# Arduino-Fio_v31.net
KiCad netlist of a schematic drawn in EAGLE
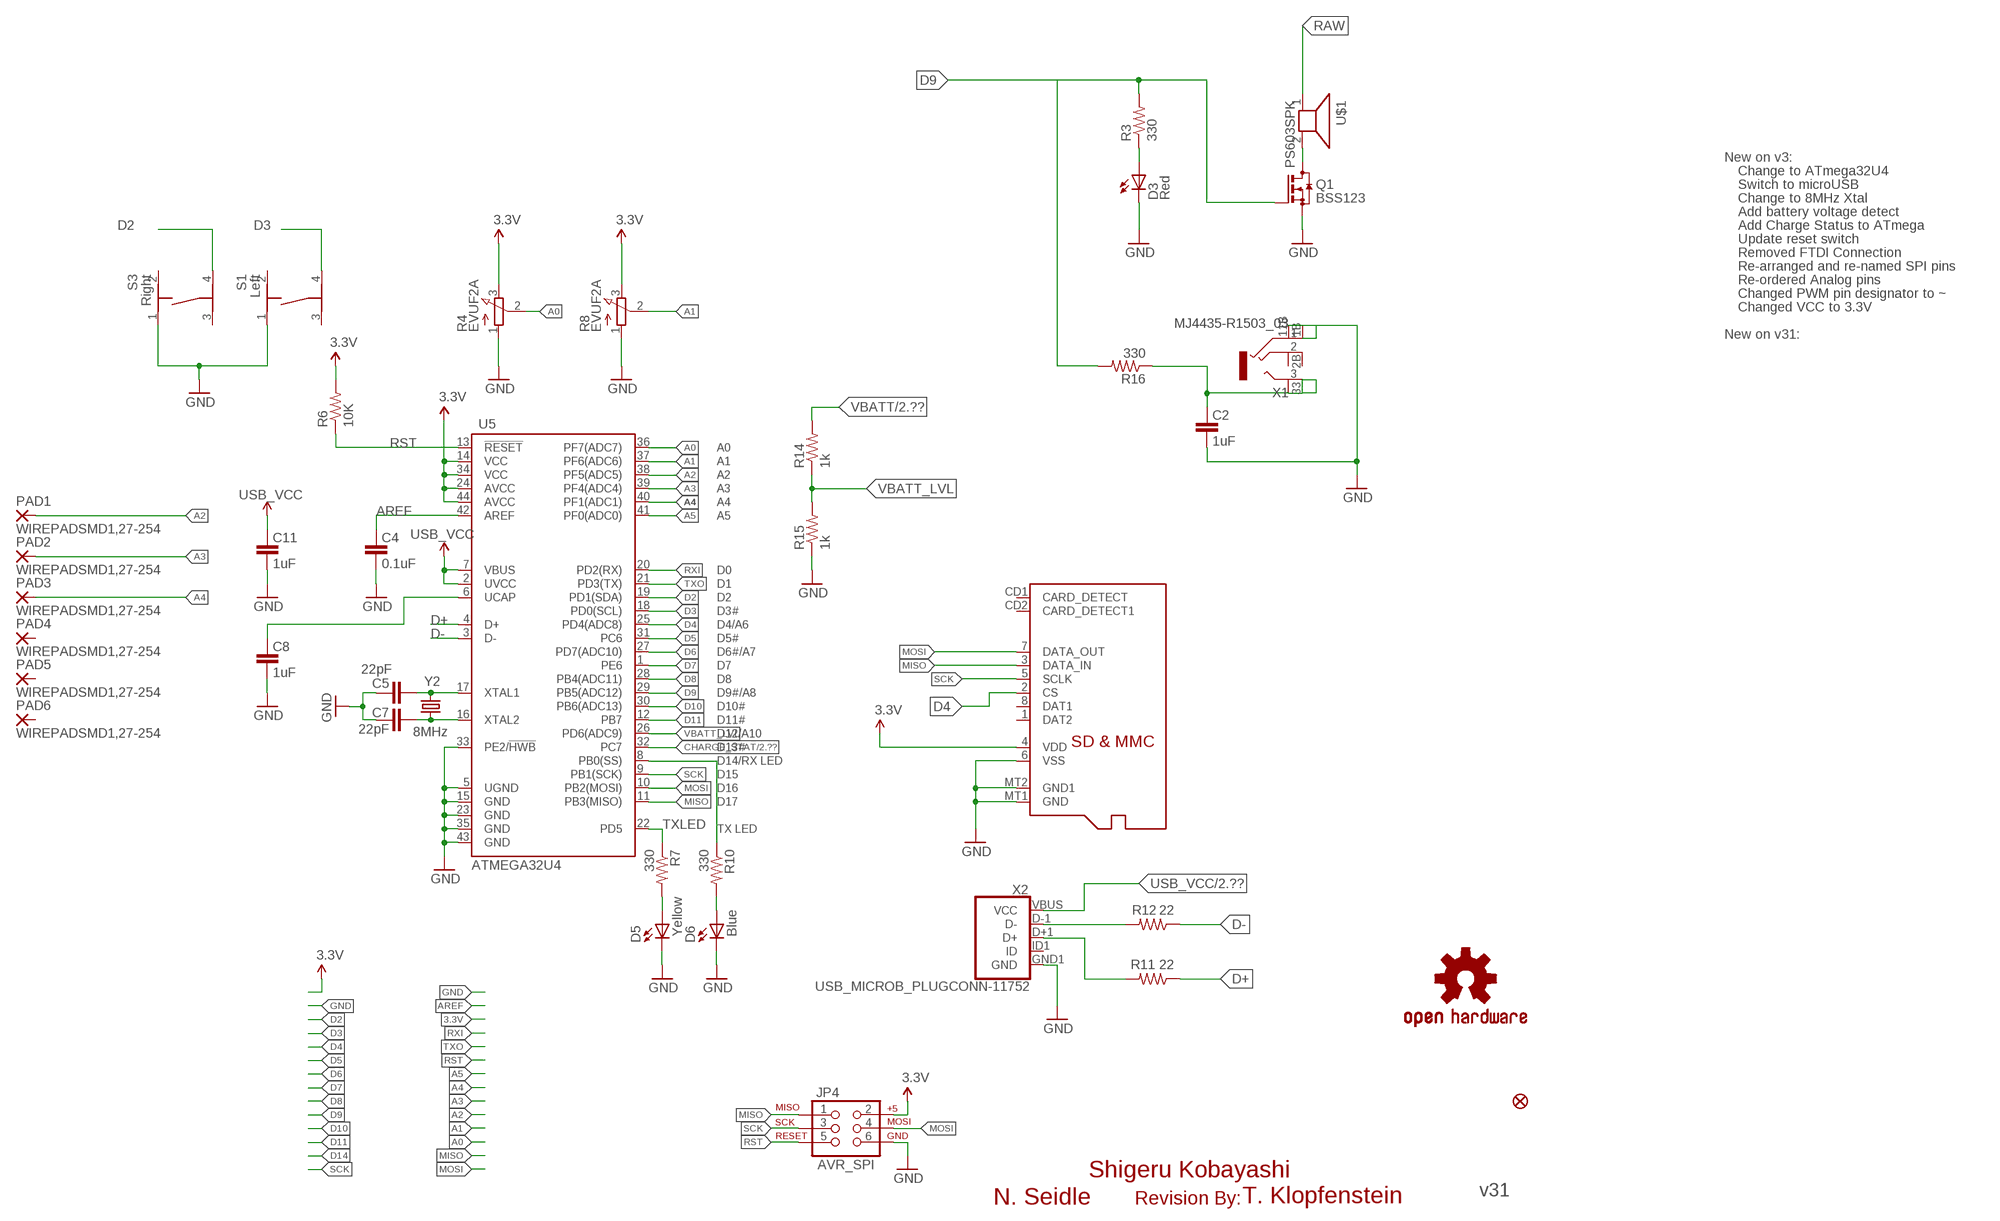
[diagram p0: schematic, sheet 1]
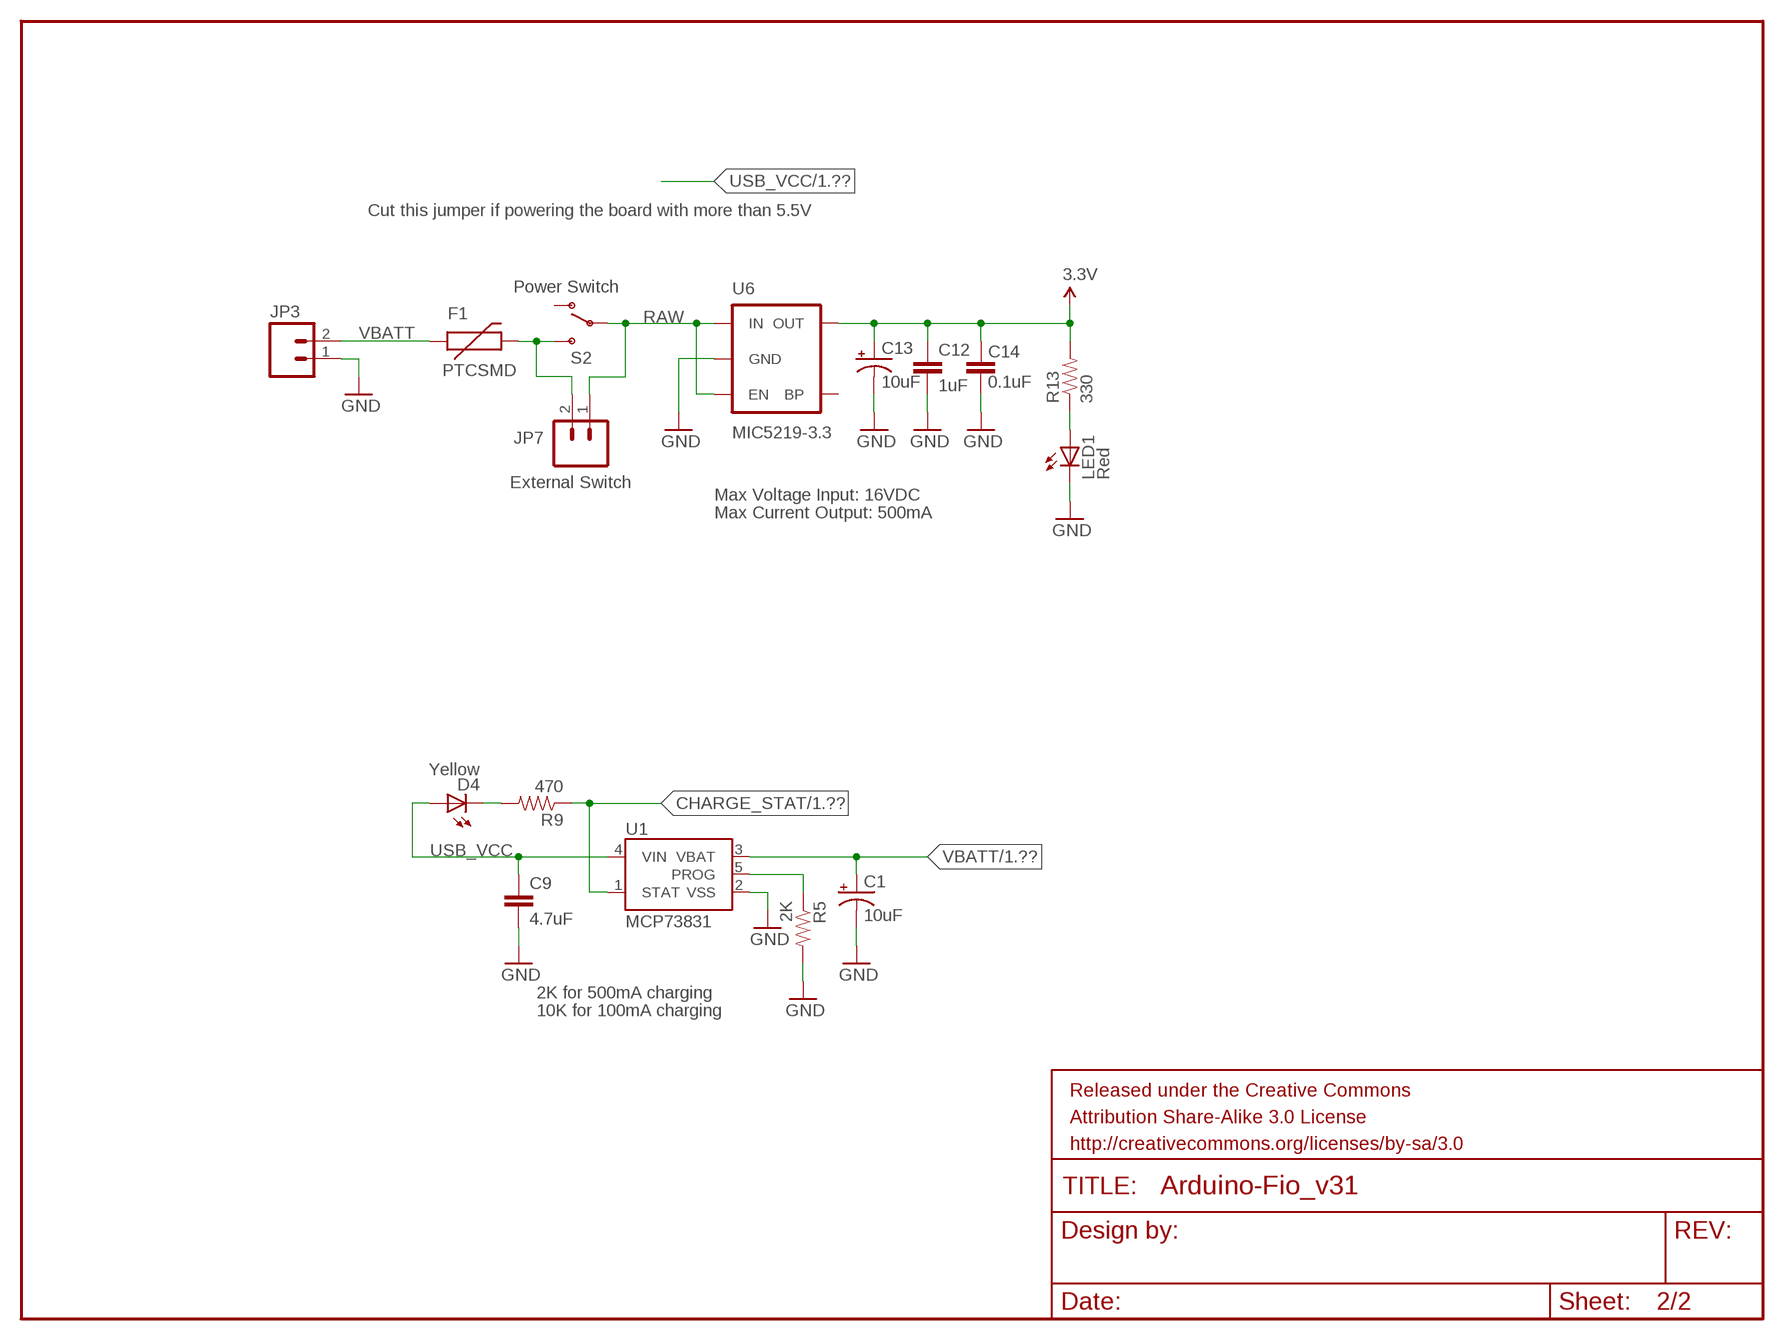
[diagram p1: schematic, sheet 2]

(export (version "E")
  (design (tool "Eeschema 10.0.6"))
  (components
    (comp (ref "C2")
      (value "1uF")
      (footprint "eagle-import:0603-CAP")
      (libsource (lib "eagle-import") (part "CAP0603-CAP"))
    )
    (comp (ref "C4")
      (value "0.1uF")
      (footprint "eagle-import:0603-CAP")
      (libsource (lib "eagle-import") (part "CAP0603-CAP"))
    )
    (comp (ref "C5")
      (value "22pF")
      (footprint "eagle-import:0603-CAP")
      (libsource (lib "eagle-import") (part "CAP0603-CAP"))
    )
    (comp (ref "C7")
      (value "22pF")
      (footprint "eagle-import:0603-CAP")
      (libsource (lib "eagle-import") (part "CAP0603-CAP"))
    )
    (comp (ref "C8")
      (value "1uF")
      (footprint "eagle-import:0603-CAP")
      (libsource (lib "eagle-import") (part "CAP0603-CAP"))
    )
    (comp (ref "C11")
      (value "1uF")
      (footprint "eagle-import:0603-CAP")
      (libsource (lib "eagle-import") (part "CAP0603-CAP"))
    )
    (comp (ref "D3")
      (value "Red")
      (footprint "eagle-import:LED-0603")
      (libsource (lib "eagle-import") (part "LED0603"))
    )
    (comp (ref "D5")
      (value "Yellow")
      (footprint "eagle-import:LED-0603")
      (libsource (lib "eagle-import") (part "LED0603"))
    )
    (comp (ref "D6")
      (value "Blue")
      (footprint "eagle-import:LED-0603")
      (libsource (lib "eagle-import") (part "LED0603"))
    )
    (comp (ref "JP4")
      (value "AVR_SPI")
      (footprint "eagle-import:2X3")
      (libsource (lib "eagle-import") (part "AVR_SPI_PRG_6PTH"))
    )
    (comp (ref "JP10")
      (value "FIDUCIALUFIDUCIAL")
      (footprint "eagle-import:FIDUCIAL-1X2")
      (libsource (lib "eagle-import") (part "FIDUCIAL1X2"))
    )
    (comp (ref "LOGO1")
      (value "OSHW-LOGOL")
      (footprint "eagle-import:OSHW-LOGO-L")
      (libsource (lib "eagle-import") (part "OSHW-LOGOL"))
    )
    (comp (ref "PAD1")
      (value "WIREPADSMD1,27-254")
      (footprint "eagle-import:SMD1,27-2,54")
      (libsource (lib "eagle-import") (part "WIREPADSMD1,27-254"))
    )
    (comp (ref "PAD2")
      (value "WIREPADSMD1,27-254")
      (footprint "eagle-import:SMD1,27-2,54")
      (libsource (lib "eagle-import") (part "WIREPADSMD1,27-254"))
    )
    (comp (ref "PAD3")
      (value "WIREPADSMD1,27-254")
      (footprint "eagle-import:SMD1,27-2,54")
      (libsource (lib "eagle-import") (part "WIREPADSMD1,27-254"))
    )
    (comp (ref "PAD4")
      (value "WIREPADSMD1,27-254")
      (footprint "eagle-import:SMD1,27-2,54")
      (libsource (lib "eagle-import") (part "WIREPADSMD1,27-254"))
    )
    (comp (ref "PAD5")
      (value "WIREPADSMD1,27-254")
      (footprint "eagle-import:SMD1,27-2,54")
      (libsource (lib "eagle-import") (part "WIREPADSMD1,27-254"))
    )
    (comp (ref "PAD6")
      (value "WIREPADSMD1,27-254")
      (footprint "eagle-import:SMD1,27-2,54")
      (libsource (lib "eagle-import") (part "WIREPADSMD1,27-254"))
    )
    (comp (ref "Q1")
      (value "BSS123")
      (footprint "eagle-import:SOT23")
      (libsource (lib "eagle-import") (part "BSS123"))
    )
    (comp (ref "R3")
      (value "330")
      (footprint "eagle-import:0603-RES")
      (libsource (lib "eagle-import") (part "RESISTOR0603-RES"))
    )
    (comp (ref "R4")
      (value "EVUF2A")
      (footprint "eagle-import:EVUF")
      (libsource (lib "eagle-import") (part "EVUAF2"))
    )
    (comp (ref "R6")
      (value "10K")
      (footprint "eagle-import:0603-RES")
      (libsource (lib "eagle-import") (part "RESISTOR0603-RES"))
    )
    (comp (ref "R7")
      (value "330")
      (footprint "eagle-import:0603-RES")
      (libsource (lib "eagle-import") (part "RESISTOR0603-RES"))
    )
    (comp (ref "R8")
      (value "EVUF2A")
      (footprint "eagle-import:EVUF")
      (libsource (lib "eagle-import") (part "EVUAF2"))
    )
    (comp (ref "R10")
      (value "330")
      (footprint "eagle-import:0603-RES")
      (libsource (lib "eagle-import") (part "RESISTOR0603-RES"))
    )
    (comp (ref "R11")
      (value "22")
      (footprint "eagle-import:0603-RES")
      (libsource (lib "eagle-import") (part "RESISTOR0603-RES"))
    )
    (comp (ref "R12")
      (value "22")
      (footprint "eagle-import:0603-RES")
      (libsource (lib "eagle-import") (part "RESISTOR0603-RES"))
    )
    (comp (ref "R14")
      (value "1k")
      (footprint "eagle-import:0603-RES")
      (libsource (lib "eagle-import") (part "RESISTOR0603-RES"))
    )
    (comp (ref "R15")
      (value "1k")
      (footprint "eagle-import:0603-RES")
      (libsource (lib "eagle-import") (part "RESISTOR0603-RES"))
    )
    (comp (ref "R16")
      (value "330")
      (footprint "eagle-import:0603-RES")
      (libsource (lib "eagle-import") (part "RESISTOR0603-RES"))
    )
    (comp (ref "S1")
      (value "Left")
      (footprint "eagle-import:TASTER-9314_SMD")
      (libsource (lib "eagle-import") (part "TASTER-9314_SMD"))
    )
    (comp (ref "S3")
      (value "Right")
      (footprint "eagle-import:TASTER-9314_SMD")
      (libsource (lib "eagle-import") (part "TASTER-9314_SMD"))
    )
    (comp (ref "U$1")
      (value "PS603SPK")
      (footprint "eagle-import:PS603")
      (libsource (lib "eagle-import") (part "PS603SPK"))
    )
    (comp (ref "U$2")
      (value "REVISION")
      (footprint "eagle-import:REVISION")
      (libsource (lib "eagle-import") (part "REVISION"))
    )
    (comp (ref "U$3")
      (value "MICROSD")
      (footprint "eagle-import:MICROSD")
      (libsource (lib "eagle-import") (part "MICROSD"))
    )
    (comp (ref "U5")
      (value "ATMEGA32U4")
      (footprint "eagle-import:QFN-44-NOPAD_1_1")
      (libsource (lib "eagle-import") (part "ATMEGA32U41{colon}1"))
    )
    (comp (ref "X1")
      (value "MJ4435-R1503_03")
      (footprint "eagle-import:1503_02")
      (libsource (lib "eagle-import") (part "MJ4435-R1503_03"))
    )
    (comp (ref "X2")
      (value "USB_MICROB_PLUGCONN-11752")
      (footprint "eagle-import:USB-B-MICRO-SMD_V03")
      (libsource (lib "eagle-import") (part "USB_MICROB_PLUGCONN-11752"))
    )
    (comp (ref "Y2")
      (value "8MHz")
      (footprint "eagle-import:CRYSTAL-SMD-5X3")
      (libsource (lib "eagle-import") (part "CRYSTAL5X3"))
    )
    (comp (ref "C1")
      (value "10uF")
      (footprint "eagle-import:EIA3216")
      (libsource (lib "eagle-import") (part "CAP_POL1206"))
    )
    (comp (ref "C9")
      (value "4.7uF")
      (footprint "eagle-import:0603-CAP")
      (libsource (lib "eagle-import") (part "CAP0603-CAP"))
    )
    (comp (ref "C12")
      (value "1uF")
      (footprint "eagle-import:0603-CAP")
      (libsource (lib "eagle-import") (part "CAP0603-CAP"))
    )
    (comp (ref "C13")
      (value "10uF")
      (footprint "eagle-import:EIA3216")
      (libsource (lib "eagle-import") (part "CAP_POL1206"))
    )
    (comp (ref "C14")
      (value "0.1uF")
      (footprint "eagle-import:0603-CAP")
      (libsource (lib "eagle-import") (part "CAP0603-CAP"))
    )
    (comp (ref "D4")
      (value "Yellow")
      (footprint "eagle-import:LED-0603")
      (libsource (lib "eagle-import") (part "LED0603"))
    )
    (comp (ref "F1")
      (value "PTCSMD")
      (footprint "eagle-import:PTC-1206")
      (libsource (lib "eagle-import") (part "PTCSMD"))
    )
    (comp (ref "FRAME2")
      (value "FRAME-LETTER")
      (footprint "eagle-import:CREATIVE_COMMONS")
      (libsource (lib "eagle-import") (part "FRAME-LETTER"))
    )
    (comp (ref "JP3")
      (value "M02-JST-2MM-SMT")
      (footprint "eagle-import:JST-2-SMD")
      (libsource (lib "eagle-import") (part "M02-JST-2MM-SMT"))
    )
    (comp (ref "JP7")
      (value "External Switch")
      (footprint "eagle-import:1X02")
      (libsource (lib "eagle-import") (part "M02PTH"))
    )
    (comp (ref "LED1")
      (value "Red")
      (footprint "eagle-import:LED-0603")
      (libsource (lib "eagle-import") (part "LED0603"))
    )
    (comp (ref "R5")
      (value "2K")
      (footprint "eagle-import:0603-RES")
      (libsource (lib "eagle-import") (part "RESISTOR0603-RES"))
    )
    (comp (ref "R9")
      (value "470")
      (footprint "eagle-import:0603-RES")
      (libsource (lib "eagle-import") (part "RESISTOR0603-RES"))
    )
    (comp (ref "R13")
      (value "330")
      (footprint "eagle-import:0603-RES")
      (libsource (lib "eagle-import") (part "RESISTOR0603-RES"))
    )
    (comp (ref "S2")
      (value "Power Switch")
      (footprint "eagle-import:AYZ0202")
      (libsource (lib "eagle-import") (part "SWITCH-SPSTSMD"))
    )
    (comp (ref "U1")
      (value "MCP73831")
      (footprint "eagle-import:SOT23-5")
      (libsource (lib "eagle-import") (part "MCP73831"))
    )
    (comp (ref "U6")
      (value "MIC5219-3.3")
      (footprint "eagle-import:SOT23-5")
      (libsource (lib "eagle-import") (part "V_REG_LDOSMD"))
    )
  )
  (nets
    (net (code "1") (name "3.3V") (class "Default")
      (node (ref "C12") (pin "1") (pinfunction "1_1") (pintype "passive"))
      (node (ref "C13") (pin "A") (pinfunction "+_A") (pintype "passive"))
      (node (ref "C14") (pin "2") (pinfunction "2_2") (pintype "passive"))
      (node (ref "JP4") (pin "2") (pinfunction "2_2") (pintype "passive"))
      (node (ref "R13") (pin "2") (pinfunction "2_2") (pintype "passive"))
      (node (ref "R4") (pin "3") (pinfunction "E_3") (pintype "passive"))
      (node (ref "R6") (pin "2") (pinfunction "2_2") (pintype "passive"))
      (node (ref "R8") (pin "3") (pinfunction "E_3") (pintype "passive"))
      (node (ref "U$3") (pin "4") (pinfunction "VDD_4") (pintype "power_in"))
      (node (ref "U5") (pin "14") (pinfunction "VCC_14") (pintype "bidirectional"))
      (node (ref "U5") (pin "24") (pinfunction "AVCC_24") (pintype "bidirectional"))
      (node (ref "U5") (pin "34") (pinfunction "VCC_34") (pintype "bidirectional"))
      (node (ref "U5") (pin "44") (pinfunction "AVCC_44") (pintype "bidirectional"))
      (node (ref "U6") (pin "5") (pinfunction "OUT_5") (pintype "passive"))
    )
    (net (code "2") (name "A0") (class "Default")
      (node (ref "R4") (pin "2") (pinfunction "S_2") (pintype "passive"))
      (node (ref "U5") (pin "36") (pinfunction "PF7(ADC7)_36") (pintype "bidirectional"))
    )
    (net (code "3") (name "A1") (class "Default")
      (node (ref "R8") (pin "2") (pinfunction "S_2") (pintype "passive"))
      (node (ref "U5") (pin "37") (pinfunction "PF6(ADC6)_37") (pintype "bidirectional"))
    )
    (net (code "4") (name "A2") (class "Default")
      (node (ref "PAD1") (pin "1") (pinfunction "P_1") (pintype "passive"))
      (node (ref "U5") (pin "38") (pinfunction "PF5(ADC5)_38") (pintype "bidirectional"))
    )
    (net (code "5") (name "A3") (class "Default")
      (node (ref "PAD2") (pin "1") (pinfunction "P_1") (pintype "passive"))
      (node (ref "U5") (pin "39") (pinfunction "PF4(ADC4)_39") (pintype "bidirectional"))
    )
    (net (code "6") (name "A4") (class "Default")
      (node (ref "PAD3") (pin "1") (pinfunction "P_1") (pintype "passive"))
      (node (ref "U5") (pin "40") (pinfunction "PF1(ADC1)_40") (pintype "bidirectional"))
    )
    (net (code "7") (name "A5") (class "Default")
      (node (ref "U5") (pin "41") (pinfunction "PF0(ADC0)_41") (pintype "bidirectional"))
    )
    (net (code "8") (name "AREF") (class "Default")
      (node (ref "C4") (pin "2") (pinfunction "2_2") (pintype "passive"))
      (node (ref "U5") (pin "42") (pinfunction "AREF_42") (pintype "bidirectional"))
    )
    (net (code "9") (name "CHARGE_STAT") (class "Default")
      (node (ref "R9") (pin "1") (pinfunction "1_1") (pintype "passive"))
      (node (ref "U1") (pin "1") (pinfunction "STAT_1") (pintype "output"))
      (node (ref "U5") (pin "32") (pinfunction "PC7_32") (pintype "bidirectional"))
    )
    (net (code "10") (name "D+") (class "Default")
      (node (ref "R11") (pin "1") (pinfunction "1_1") (pintype "passive"))
      (node (ref "U5") (pin "4") (pinfunction "D+_4") (pintype "bidirectional"))
    )
    (net (code "11") (name "D-") (class "Default")
      (node (ref "R12") (pin "1") (pinfunction "1_1") (pintype "passive"))
      (node (ref "U5") (pin "3") (pinfunction "D-_3") (pintype "bidirectional"))
    )
    (net (code "12") (name "D2") (class "Default")
      (node (ref "S3") (pin "4") (pinfunction "4_4") (pintype "passive"))
      (node (ref "U5") (pin "19") (pinfunction "PD1(SDA)_19") (pintype "bidirectional"))
    )
    (net (code "13") (name "D3") (class "Default")
      (node (ref "S1") (pin "4") (pinfunction "4_4") (pintype "passive"))
      (node (ref "U5") (pin "18") (pinfunction "PD0(SCL)_18") (pintype "bidirectional"))
    )
    (net (code "14") (name "D4") (class "Default")
      (node (ref "U$3") (pin "2") (pinfunction "CS_2") (pintype "input"))
      (node (ref "U5") (pin "25") (pinfunction "PD4(ADC8)_25") (pintype "bidirectional"))
    )
    (net (code "15") (name "D5") (class "Default")
      (node (ref "U5") (pin "31") (pinfunction "PC6_31") (pintype "bidirectional"))
    )
    (net (code "16") (name "D6") (class "Default")
      (node (ref "U5") (pin "27") (pinfunction "PD7(ADC10)_27") (pintype "bidirectional"))
    )
    (net (code "17") (name "D7") (class "Default")
      (node (ref "U5") (pin "1") (pinfunction "PE6_1") (pintype "bidirectional"))
    )
    (net (code "18") (name "D8") (class "Default")
      (node (ref "U5") (pin "28") (pinfunction "PB4(ADC11)_28") (pintype "bidirectional"))
    )
    (net (code "19") (name "D9") (class "Default")
      (node (ref "Q1") (pin "1") (pinfunction "G_1") (pintype "passive"))
      (node (ref "R16") (pin "2") (pinfunction "2_2") (pintype "passive"))
      (node (ref "R3") (pin "2") (pinfunction "2_2") (pintype "passive"))
      (node (ref "U5") (pin "29") (pinfunction "PB5(ADC12)_29") (pintype "bidirectional"))
    )
    (net (code "20") (name "D10") (class "Default")
      (node (ref "U5") (pin "30") (pinfunction "PB6(ADC13)_30") (pintype "bidirectional"))
    )
    (net (code "21") (name "D11") (class "Default")
      (node (ref "U5") (pin "12") (pinfunction "PB7_12") (pintype "bidirectional"))
    )
    (net (code "22") (name "D14") (class "Default")
      (node (ref "R10") (pin "1") (pinfunction "1_1") (pintype "passive"))
      (node (ref "U5") (pin "8") (pinfunction "PB0(SS)_8") (pintype "bidirectional"))
    )
    (net (code "23") (name "GND") (class "Default")
      (node (ref "C1") (pin "C") (pinfunction "-_C") (pintype "passive"))
      (node (ref "C11") (pin "1") (pinfunction "1_1") (pintype "passive"))
      (node (ref "C12") (pin "2") (pinfunction "2_2") (pintype "passive"))
      (node (ref "C13") (pin "C") (pinfunction "-_C") (pintype "passive"))
      (node (ref "C14") (pin "1") (pinfunction "1_1") (pintype "passive"))
      (node (ref "C2") (pin "1") (pinfunction "1_1") (pintype "passive"))
      (node (ref "C4") (pin "1") (pinfunction "1_1") (pintype "passive"))
      (node (ref "C5") (pin "2") (pinfunction "2_2") (pintype "passive"))
      (node (ref "C7") (pin "2") (pinfunction "2_2") (pintype "passive"))
      (node (ref "C8") (pin "1") (pinfunction "1_1") (pintype "passive"))
      (node (ref "C9") (pin "2") (pinfunction "2_2") (pintype "passive"))
      (node (ref "D3") (pin "C") (pinfunction "C_C") (pintype "passive"))
      (node (ref "D5") (pin "C") (pinfunction "C_C") (pintype "passive"))
      (node (ref "D6") (pin "C") (pinfunction "C_C") (pintype "passive"))
      (node (ref "JP3") (pin "1") (pinfunction "1_1") (pintype "passive"))
      (node (ref "JP4") (pin "6") (pinfunction "6_6") (pintype "passive"))
      (node (ref "LED1") (pin "C") (pinfunction "C_C") (pintype "passive"))
      (node (ref "Q1") (pin "2") (pinfunction "S_2") (pintype "passive"))
      (node (ref "R15") (pin "1") (pinfunction "1_1") (pintype "passive"))
      (node (ref "R4") (pin "1") (pinfunction "A_1") (pintype "passive"))
      (node (ref "R5") (pin "2") (pinfunction "2_2") (pintype "passive"))
      (node (ref "R8") (pin "1") (pinfunction "A_1") (pintype "passive"))
      (node (ref "S1") (pin "1") (pinfunction "1_1") (pintype "passive"))
      (node (ref "S3") (pin "1") (pinfunction "1_1") (pintype "passive"))
      (node (ref "U$3") (pin "6") (pinfunction "VSS_6") (pintype "power_in"))
      (node (ref "U$3") (pin "MT1") (pinfunction "GND_MT1") (pintype "power_in"))
      (node (ref "U$3") (pin "MT2") (pinfunction "GND1_MT2") (pintype "power_in"))
      (node (ref "U1") (pin "2") (pinfunction "VSS_2") (pintype "power_in"))
      (node (ref "U5") (pin "15") (pinfunction "GND_15") (pintype "bidirectional"))
      (node (ref "U5") (pin "23") (pinfunction "GND_23") (pintype "bidirectional"))
      (node (ref "U5") (pin "33") (pinfunction "PE2/~{HWB}_33") (pintype "bidirectional"))
      (node (ref "U5") (pin "35") (pinfunction "GND_35") (pintype "bidirectional"))
      (node (ref "U5") (pin "43") (pinfunction "GND_43") (pintype "bidirectional"))
      (node (ref "U5") (pin "5") (pinfunction "UGND_5") (pintype "bidirectional"))
      (node (ref "U6") (pin "2") (pinfunction "GND_2") (pintype "input"))
      (node (ref "X1") (pin "1") (pinfunction "1_1_1") (pintype "passive"))
      (node (ref "X1") (pin "11B") (pinfunction "1_4_11B") (pintype "passive"))
      (node (ref "X1") (pin "1B") (pinfunction "1_3_1B") (pintype "passive"))
      (node (ref "X2") (pin "GND1") (pinfunction "GND_GND1") (pintype "bidirectional"))
    )
    (net (code "24") (name "MISO") (class "Default")
      (node (ref "JP4") (pin "1") (pinfunction "1_1") (pintype "passive"))
      (node (ref "U$3") (pin "3") (pinfunction "DATA_IN_3") (pintype "input"))
      (node (ref "U5") (pin "11") (pinfunction "PB3(MISO)_11") (pintype "bidirectional"))
    )
    (net (code "25") (name "MOSI") (class "Default")
      (node (ref "JP4") (pin "4") (pinfunction "4_4") (pintype "passive"))
      (node (ref "U$3") (pin "7") (pinfunction "DATA_OUT_7") (pintype "output"))
      (node (ref "U5") (pin "10") (pinfunction "PB2(MOSI)_10") (pintype "bidirectional"))
    )
    (net (code "26") (name "Net-(D3-PadA)") (class "Default")
      (node (ref "D3") (pin "A") (pinfunction "A_A") (pintype "passive"))
      (node (ref "R3") (pin "1") (pinfunction "1_1") (pintype "passive"))
    )
    (net (code "27") (name "Net-(D4-PadC)") (class "Default")
      (node (ref "D4") (pin "C") (pinfunction "C_C") (pintype "passive"))
      (node (ref "R9") (pin "2") (pinfunction "2_2") (pintype "passive"))
    )
    (net (code "28") (name "Net-(D5-PadA)") (class "Default")
      (node (ref "D5") (pin "A") (pinfunction "A_A") (pintype "passive"))
      (node (ref "R7") (pin "2") (pinfunction "2_2") (pintype "passive"))
    )
    (net (code "29") (name "Net-(D6-PadA)") (class "Default")
      (node (ref "D6") (pin "A") (pinfunction "A_A") (pintype "passive"))
      (node (ref "R10") (pin "2") (pinfunction "2_2") (pintype "passive"))
    )
    (net (code "30") (name "Net-(LED1-PadA)") (class "Default")
      (node (ref "LED1") (pin "A") (pinfunction "A_A") (pintype "passive"))
      (node (ref "R13") (pin "1") (pinfunction "1_1") (pintype "passive"))
    )
    (net (code "31") (name "Net-(Q1-D)") (class "Default")
      (node (ref "Q1") (pin "3") (pinfunction "D_3") (pintype "passive"))
      (node (ref "U$1") (pin "2") (pinfunction "2_2") (pintype "passive"))
    )
    (net (code "32") (name "Net-(S2-S)") (class "Default")
      (node (ref "F1") (pin "2") (pinfunction "2_2") (pintype "bidirectional"))
      (node (ref "JP7") (pin "2") (pinfunction "2_2") (pintype "passive"))
      (node (ref "S2") (pin "3") (pinfunction "S_3") (pintype "passive"))
    )
    (net (code "33") (name "Net-(U1-PROG)") (class "Default")
      (node (ref "R5") (pin "1") (pinfunction "1_1") (pintype "passive"))
      (node (ref "U1") (pin "5") (pinfunction "PROG_5") (pintype "input"))
    )
    (net (code "34") (name "Net-(U5-UCAP)") (class "Default")
      (node (ref "C8") (pin "2") (pinfunction "2_2") (pintype "passive"))
      (node (ref "U5") (pin "6") (pinfunction "UCAP_6") (pintype "bidirectional"))
    )
    (net (code "35") (name "Net-(U5-XTAL1)") (class "Default")
      (node (ref "C5") (pin "1") (pinfunction "1_1") (pintype "passive"))
      (node (ref "U5") (pin "17") (pinfunction "XTAL1_17") (pintype "bidirectional"))
      (node (ref "Y2") (pin "3") (pinfunction "2_3") (pintype "passive"))
    )
    (net (code "36") (name "Net-(U5-XTAL2)") (class "Default")
      (node (ref "C7") (pin "1") (pinfunction "1_1") (pintype "passive"))
      (node (ref "U5") (pin "16") (pinfunction "XTAL2_16") (pintype "bidirectional"))
      (node (ref "Y2") (pin "1") (pinfunction "1_1") (pintype "passive"))
    )
    (net (code "37") (name "Net-(X1-3_1)") (class "Default")
      (node (ref "C2") (pin "2") (pinfunction "2_2") (pintype "passive"))
      (node (ref "R16") (pin "1") (pinfunction "1_1") (pintype "passive"))
      (node (ref "X1") (pin "3") (pinfunction "3_1_3") (pintype "passive"))
      (node (ref "X1") (pin "33") (pinfunction "3_3_33") (pintype "passive"))
      (node (ref "X1") (pin "33B") (pinfunction "3_4_33B") (pintype "passive"))
    )
    (net (code "38") (name "Net-(X2-D+)") (class "Default")
      (node (ref "R11") (pin "2") (pinfunction "2_2") (pintype "passive"))
      (node (ref "X2") (pin "D+1") (pinfunction "D+_D+1") (pintype "bidirectional"))
    )
    (net (code "39") (name "Net-(X2-D-)") (class "Default")
      (node (ref "R12") (pin "2") (pinfunction "2_2") (pintype "passive"))
      (node (ref "X2") (pin "D-1") (pinfunction "D-_D-1") (pintype "bidirectional"))
    )
    (net (code "40") (name "RAW") (class "Default")
      (node (ref "JP7") (pin "1") (pinfunction "1_1") (pintype "passive"))
      (node (ref "S2") (pin "2") (pinfunction "P_2") (pintype "passive"))
      (node (ref "U$1") (pin "1") (pinfunction "1_1") (pintype "passive"))
      (node (ref "U6") (pin "1") (pinfunction "IN_1") (pintype "input"))
      (node (ref "U6") (pin "3") (pinfunction "EN_3") (pintype "input"))
    )
    (net (code "41") (name "RST") (class "Default")
      (node (ref "JP4") (pin "5") (pinfunction "5_5") (pintype "passive"))
      (node (ref "R6") (pin "1") (pinfunction "1_1") (pintype "passive"))
      (node (ref "U5") (pin "13") (pinfunction "~{RESET}_13") (pintype "bidirectional"))
    )
    (net (code "42") (name "RXI") (class "Default")
      (node (ref "U5") (pin "20") (pinfunction "PD2(RX)_20") (pintype "bidirectional"))
    )
    (net (code "43") (name "SCK") (class "Default")
      (node (ref "JP4") (pin "3") (pinfunction "3_3") (pintype "passive"))
      (node (ref "U$3") (pin "5") (pinfunction "SCLK_5") (pintype "input"))
      (node (ref "U5") (pin "9") (pinfunction "PB1(SCK)_9") (pintype "bidirectional"))
    )
    (net (code "44") (name "TXLED") (class "Default")
      (node (ref "R7") (pin "1") (pinfunction "1_1") (pintype "passive"))
      (node (ref "U5") (pin "22") (pinfunction "PD5_22") (pintype "bidirectional"))
    )
    (net (code "45") (name "TXO") (class "Default")
      (node (ref "U5") (pin "21") (pinfunction "PD3(TX)_21") (pintype "bidirectional"))
    )
    (net (code "46") (name "USB_VCC") (class "Default")
      (node (ref "C11") (pin "2") (pinfunction "2_2") (pintype "passive"))
      (node (ref "C9") (pin "1") (pinfunction "1_1") (pintype "passive"))
      (node (ref "D4") (pin "A") (pinfunction "A_A") (pintype "passive"))
      (node (ref "U1") (pin "4") (pinfunction "VIN_4") (pintype "power_in"))
      (node (ref "U5") (pin "2") (pinfunction "UVCC_2") (pintype "bidirectional"))
      (node (ref "U5") (pin "7") (pinfunction "VBUS_7") (pintype "bidirectional"))
      (node (ref "X2") (pin "VBUS") (pinfunction "VCC_VBUS") (pintype "bidirectional"))
    )
    (net (code "47") (name "VBATT") (class "Default")
      (node (ref "C1") (pin "A") (pinfunction "+_A") (pintype "passive"))
      (node (ref "F1") (pin "1") (pinfunction "1_1") (pintype "bidirectional"))
      (node (ref "JP3") (pin "2") (pinfunction "2_2") (pintype "passive"))
      (node (ref "R14") (pin "2") (pinfunction "2_2") (pintype "passive"))
      (node (ref "U1") (pin "3") (pinfunction "VBAT_3") (pintype "power_in"))
    )
    (net (code "48") (name "VBATT_LVL") (class "Default")
      (node (ref "R14") (pin "1") (pinfunction "1_1") (pintype "passive"))
      (node (ref "R15") (pin "2") (pinfunction "2_2") (pintype "passive"))
      (node (ref "U5") (pin "26") (pinfunction "PD6(ADC9)_26") (pintype "bidirectional"))
    )
    (net (code "49") (name "unconnected-(PAD4-P-Pad1)") (class "Default")
      (node (ref "PAD4") (pin "1") (pinfunction "P_1") (pintype "passive"))
    )
    (net (code "50") (name "unconnected-(PAD5-P-Pad1)") (class "Default")
      (node (ref "PAD5") (pin "1") (pinfunction "P_1") (pintype "passive"))
    )
    (net (code "51") (name "unconnected-(PAD6-P-Pad1)") (class "Default")
      (node (ref "PAD6") (pin "1") (pinfunction "P_1") (pintype "passive"))
    )
    (net (code "52") (name "unconnected-(S1-Pad2)") (class "Default")
      (node (ref "S1") (pin "2") (pinfunction "2_2") (pintype "passive"))
    )
    (net (code "53") (name "unconnected-(S1-Pad3)") (class "Default")
      (node (ref "S1") (pin "3") (pinfunction "3_3") (pintype "passive"))
    )
    (net (code "54") (name "unconnected-(S2-O-Pad1)") (class "Default")
      (node (ref "S2") (pin "1") (pinfunction "O_1") (pintype "passive"))
    )
    (net (code "55") (name "unconnected-(S3-Pad2)") (class "Default")
      (node (ref "S3") (pin "2") (pinfunction "2_2") (pintype "passive"))
    )
    (net (code "56") (name "unconnected-(S3-Pad3)") (class "Default")
      (node (ref "S3") (pin "3") (pinfunction "3_3") (pintype "passive"))
    )
    (net (code "57") (name "unconnected-(U$3-CARD_DETECT-PadCD1)") (class "Default")
      (node (ref "U$3") (pin "CD1") (pinfunction "CARD_DETECT_CD1") (pintype "passive"))
    )
    (net (code "58") (name "unconnected-(U$3-CARD_DETECT1-PadCD2)") (class "Default")
      (node (ref "U$3") (pin "CD2") (pinfunction "CARD_DETECT1_CD2") (pintype "passive"))
    )
    (net (code "59") (name "unconnected-(U$3-DAT1-Pad8)") (class "Default")
      (node (ref "U$3") (pin "8") (pinfunction "DAT1_8") (pintype "bidirectional"))
    )
    (net (code "60") (name "unconnected-(U$3-DAT2-Pad1)") (class "Default")
      (node (ref "U$3") (pin "1") (pinfunction "DAT2_1") (pintype "bidirectional"))
    )
    (net (code "61") (name "unconnected-(U6-BP-Pad4)") (class "Default")
      (node (ref "U6") (pin "4") (pinfunction "BP_4") (pintype "input"))
    )
    (net (code "62") (name "unconnected-(X1-1_2-Pad11)") (class "Default")
      (node (ref "X1") (pin "11") (pinfunction "1_2_11") (pintype "passive"))
    )
    (net (code "63") (name "unconnected-(X1-2_1-Pad2)") (class "Default")
      (node (ref "X1") (pin "2") (pinfunction "2_1_2") (pintype "passive"))
    )
    (net (code "64") (name "unconnected-(X1-2_2-Pad22)") (class "Default")
      (node (ref "X1") (pin "22") (pinfunction "2_2_22") (pintype "passive"))
    )
    (net (code "65") (name "unconnected-(X1-2_3-Pad2B)") (class "Default")
      (node (ref "X1") (pin "2B") (pinfunction "2_3_2B") (pintype "passive"))
    )
    (net (code "66") (name "unconnected-(X1-2_4-Pad22B)") (class "Default")
      (node (ref "X1") (pin "22B") (pinfunction "2_4_22B") (pintype "passive"))
    )
    (net (code "67") (name "unconnected-(X1-3_2-Pad3B)") (class "Default")
      (node (ref "X1") (pin "3B") (pinfunction "3_2_3B") (pintype "passive"))
    )
    (net (code "68") (name "unconnected-(X2-ID-PadID1)") (class "Default")
      (node (ref "X2") (pin "ID1") (pinfunction "ID_ID1") (pintype "bidirectional"))
    )
  )
)
